# TOP.net
KiCad netlist of a schematic drawn in Altium Designer
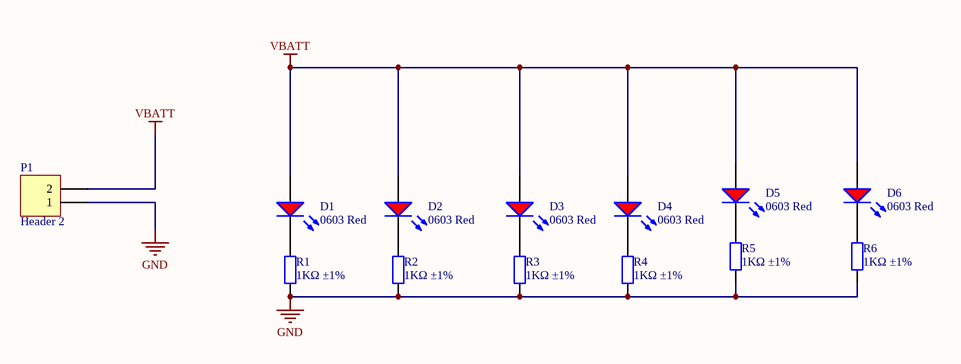
[diagram p0: TOP.SchDoc]

(export (version "E")
  (design (tool "Eeschema 10.0.6"))
  (components
    (comp (ref "D1")
      (value "0603 Red")
      (footprint "0603_LED_S1")
      (description "LED")
      (libsource (lib "LED") (part "0603 LED Red"))
    )
    (comp (ref "D2")
      (value "0603 Red")
      (footprint "0603_LED_S1")
      (description "LED")
      (libsource (lib "LED") (part "0603 LED Red"))
    )
    (comp (ref "D3")
      (value "0603 Red")
      (footprint "0603_LED_S1")
      (description "LED")
      (libsource (lib "LED") (part "0603 LED Red"))
    )
    (comp (ref "D4")
      (value "0603 Red")
      (footprint "0603_LED_S1")
      (description "LED")
      (libsource (lib "LED") (part "0603 LED Red"))
    )
    (comp (ref "D5")
      (value "0603 Red")
      (footprint "0603_LED_S1")
      (description "LED")
      (libsource (lib "LED") (part "0603 LED Red"))
    )
    (comp (ref "D6")
      (value "0603 Red")
      (footprint "0603_LED_S1")
      (description "LED")
      (libsource (lib "LED") (part "0603 LED Red"))
    )
    (comp (ref "P1")
      (value "Header 2")
      (footprint "HDR1X2")
      (description "Header, 2-Pin")
      (fields (field (name "PUBLISHER") "Altium Limited"))
      (libsource (lib "Miscellaneous Connectors") (part "Header 2"))
    )
    (comp (ref "R1")
      (value "1KΩ ±1%")
      (footprint "0402_R")
      (description "Chip resistor")
      (fields (field (name "MANUFACTURER") "Uniroyal Elec") (field (name "PARTNUMBER") "0402WGF1001TCE"))
      (libsource (lib "RES") (part "0402 1K (1001) 1%"))
    )
    (comp (ref "R2")
      (value "1KΩ ±1%")
      (footprint "0402_R")
      (description "Chip resistor")
      (fields (field (name "MANUFACTURER") "Uniroyal Elec") (field (name "PARTNUMBER") "0402WGF1001TCE"))
      (libsource (lib "RES") (part "0402 1K (1001) 1%"))
    )
    (comp (ref "R3")
      (value "1KΩ ±1%")
      (footprint "0402_R")
      (description "Chip resistor")
      (fields (field (name "MANUFACTURER") "Uniroyal Elec") (field (name "PARTNUMBER") "0402WGF1001TCE"))
      (libsource (lib "RES") (part "0402 1K (1001) 1%"))
    )
    (comp (ref "R4")
      (value "1KΩ ±1%")
      (footprint "0402_R")
      (description "Chip resistor")
      (fields (field (name "MANUFACTURER") "Uniroyal Elec") (field (name "PARTNUMBER") "0402WGF1001TCE"))
      (libsource (lib "RES") (part "0402 1K (1001) 1%"))
    )
    (comp (ref "R5")
      (value "1KΩ ±1%")
      (footprint "0402_R")
      (description "Chip resistor")
      (fields (field (name "MANUFACTURER") "Uniroyal Elec") (field (name "PARTNUMBER") "0402WGF1001TCE"))
      (libsource (lib "RES") (part "0402 1K (1001) 1%"))
    )
    (comp (ref "R6")
      (value "1KΩ ±1%")
      (footprint "0402_R")
      (description "Chip resistor")
      (fields (field (name "MANUFACTURER") "Uniroyal Elec") (field (name "PARTNUMBER") "0402WGF1001TCE"))
      (libsource (lib "RES") (part "0402 1K (1001) 1%"))
    )
  )
  (nets
    (net (code "1") (name "GND") (class "Default")
      (node (ref "P1") (pin "1") (pinfunction "1_1") (pintype "passive"))
      (node (ref "R1") (pin "1") (pinfunction "1_1") (pintype "passive"))
      (node (ref "R2") (pin "1") (pinfunction "1_1") (pintype "passive"))
      (node (ref "R3") (pin "1") (pinfunction "1_1") (pintype "passive"))
      (node (ref "R4") (pin "1") (pinfunction "1_1") (pintype "passive"))
      (node (ref "R5") (pin "1") (pinfunction "1_1") (pintype "passive"))
      (node (ref "R6") (pin "1") (pinfunction "1_1") (pintype "passive"))
    )
    (net (code "2") (name "Net-(D1-PadK)") (class "Default")
      (node (ref "D1") (pin "K") (pinfunction "K_K") (pintype "passive"))
      (node (ref "R1") (pin "2") (pinfunction "2_2") (pintype "passive"))
    )
    (net (code "3") (name "Net-(D2-PadK)") (class "Default")
      (node (ref "D2") (pin "K") (pinfunction "K_K") (pintype "passive"))
      (node (ref "R2") (pin "2") (pinfunction "2_2") (pintype "passive"))
    )
    (net (code "4") (name "Net-(D3-PadK)") (class "Default")
      (node (ref "D3") (pin "K") (pinfunction "K_K") (pintype "passive"))
      (node (ref "R3") (pin "2") (pinfunction "2_2") (pintype "passive"))
    )
    (net (code "5") (name "Net-(D4-PadK)") (class "Default")
      (node (ref "D4") (pin "K") (pinfunction "K_K") (pintype "passive"))
      (node (ref "R4") (pin "2") (pinfunction "2_2") (pintype "passive"))
    )
    (net (code "6") (name "Net-(D5-PadK)") (class "Default")
      (node (ref "D5") (pin "K") (pinfunction "K_K") (pintype "passive"))
      (node (ref "R5") (pin "2") (pinfunction "2_2") (pintype "passive"))
    )
    (net (code "7") (name "Net-(D6-PadK)") (class "Default")
      (node (ref "D6") (pin "K") (pinfunction "K_K") (pintype "passive"))
      (node (ref "R6") (pin "2") (pinfunction "2_2") (pintype "passive"))
    )
    (net (code "8") (name "VBATT") (class "Default")
      (node (ref "D1") (pin "A") (pinfunction "A_A") (pintype "passive"))
      (node (ref "D2") (pin "A") (pinfunction "A_A") (pintype "passive"))
      (node (ref "D3") (pin "A") (pinfunction "A_A") (pintype "passive"))
      (node (ref "D4") (pin "A") (pinfunction "A_A") (pintype "passive"))
      (node (ref "D5") (pin "A") (pinfunction "A_A") (pintype "passive"))
      (node (ref "D6") (pin "A") (pinfunction "A_A") (pintype "passive"))
      (node (ref "P1") (pin "2") (pinfunction "2_2") (pintype "passive"))
    )
  )
)
